# Sheet-watch.net
KiCad netlist of a schematic drawn in Altium Designer
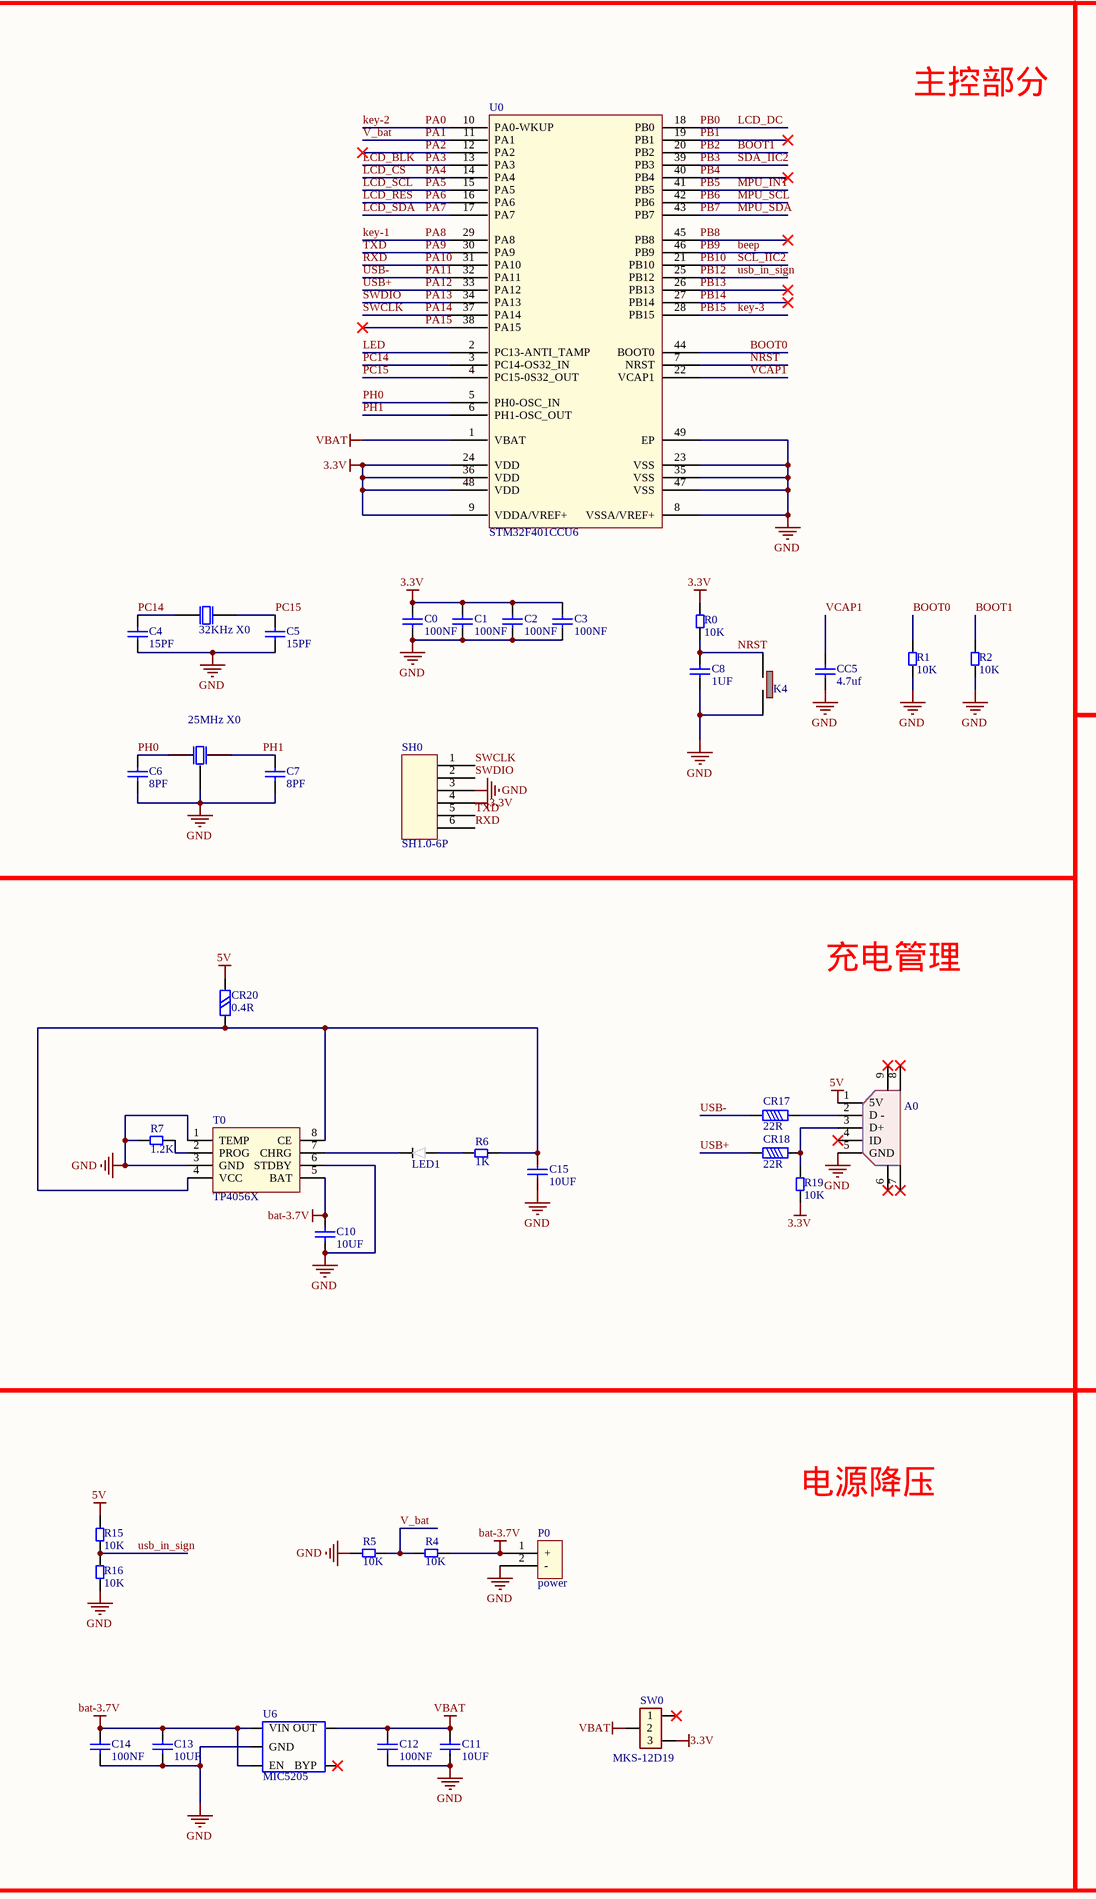
[diagram p0: Sheet-watch.SchDoc, left]
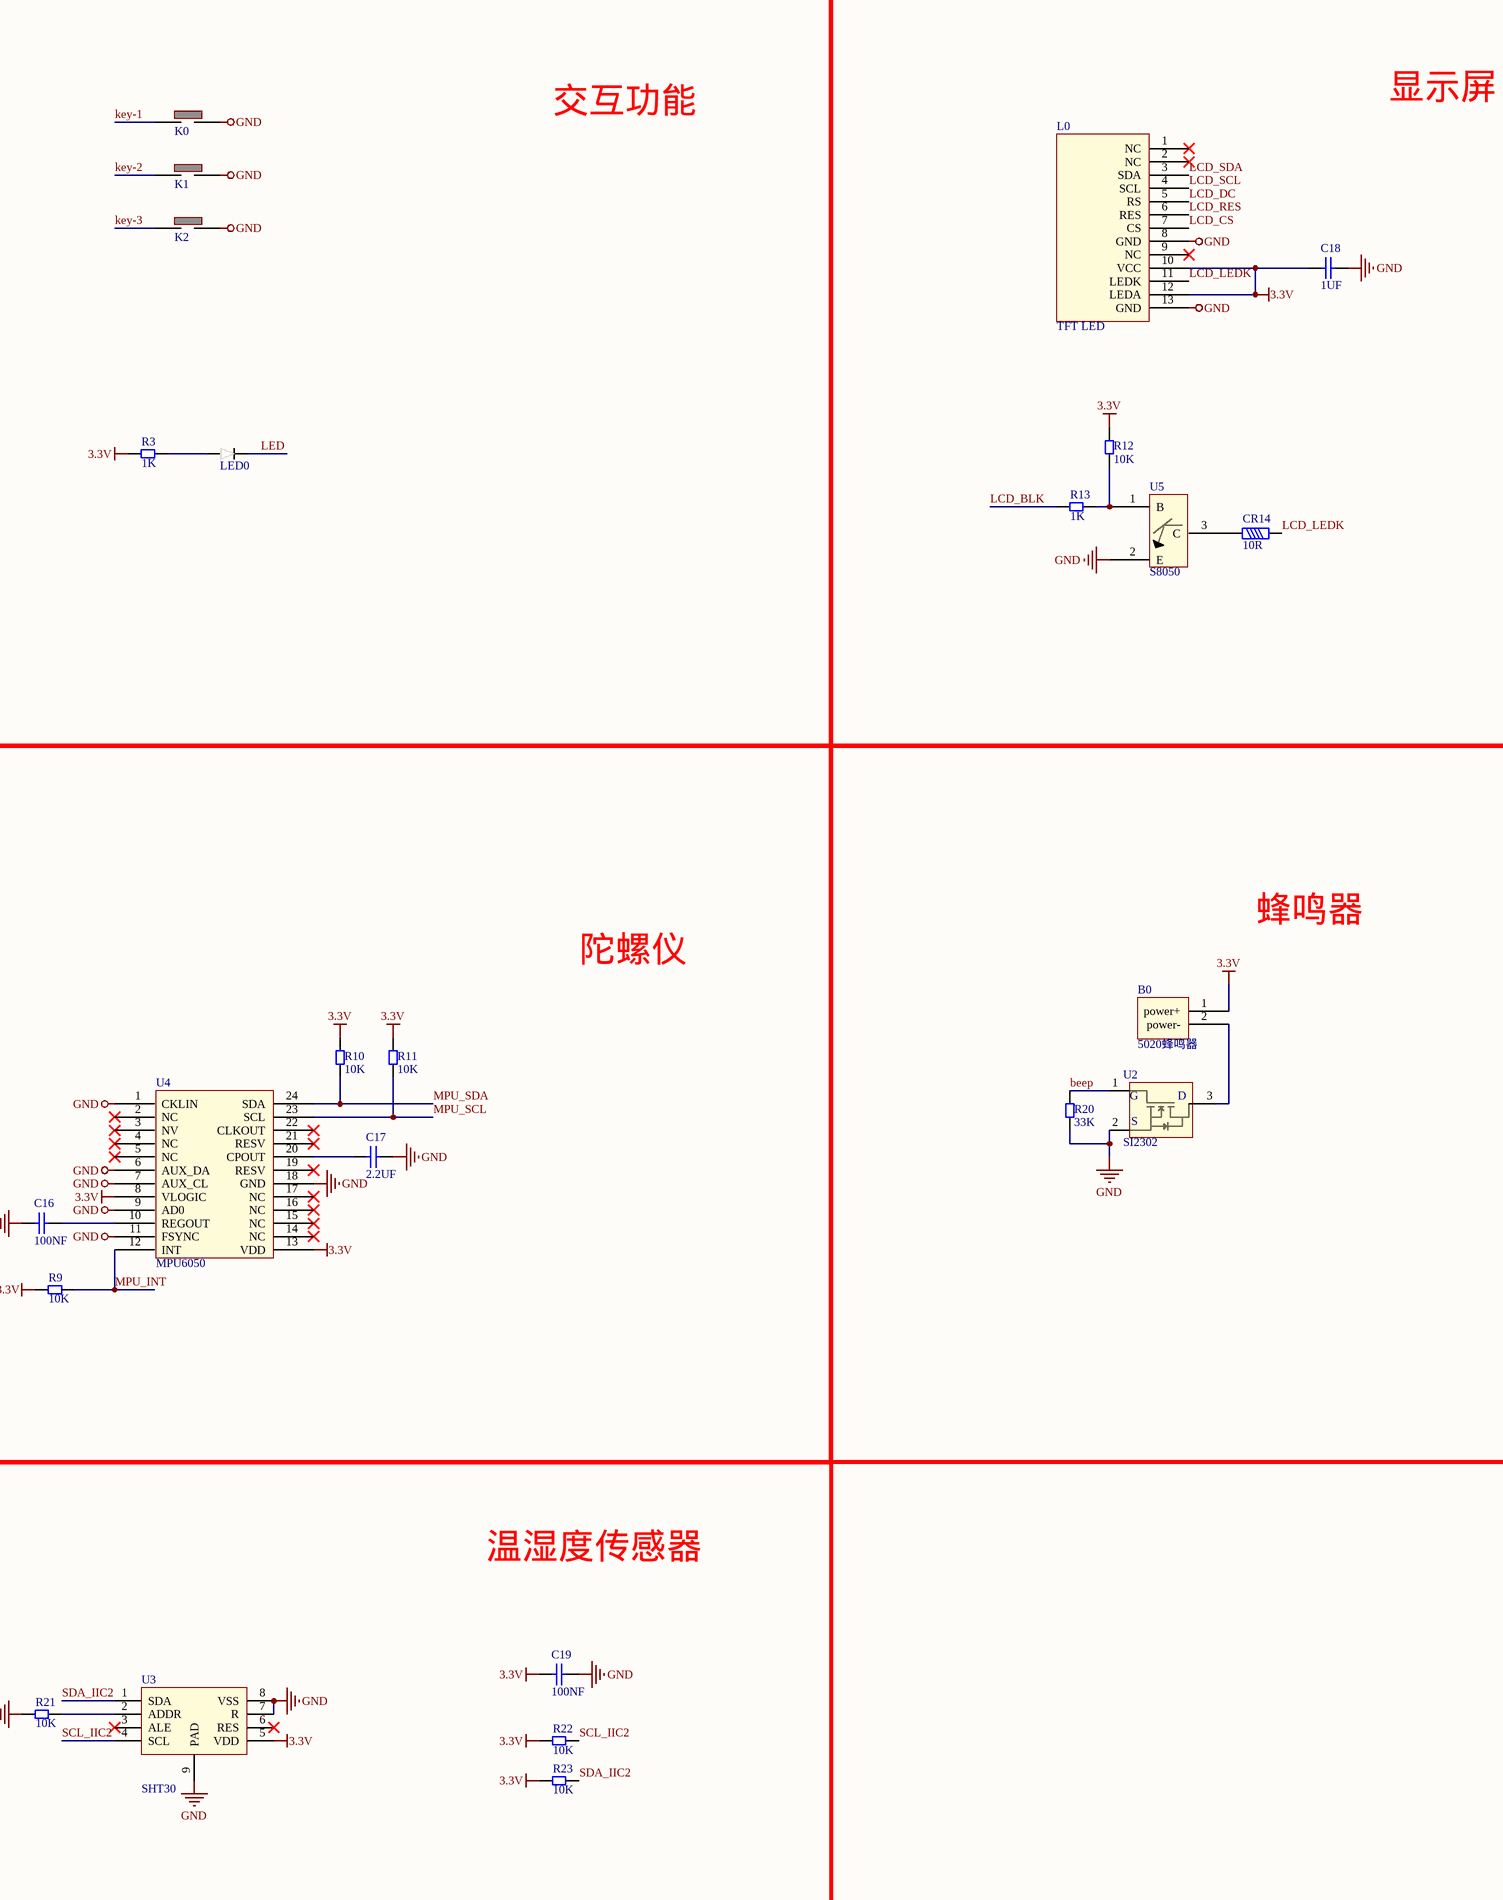
[diagram p1: Sheet-watch.SchDoc, right]

(export (version "E")
  (design (tool "Eeschema 10.0.6"))
  (components
    (comp (ref "25MHz X0")
      (value "XTAL 3225 8M")
      (footprint "T 3225")
      (libsource (lib "tianxiaohua_Schlib") (part "XTAL 3225 8M"))
    )
    (comp (ref "32KHz X0")
      (value "XTAL 3215 32.768kKHz")
      (footprint "T 3215")
      (libsource (lib "tianxiaohua_Schlib") (part "XTAL 3215 32.768kKHz"))
    )
    (comp (ref "A0")
      (value "Micro USB")
      (footprint "Micro usb AB")
      (libsource (lib "tianxiaohua_Schlib") (part "Micro USB"))
    )
    (comp (ref "B0")
      (value "5020蜂鸣器")
      (footprint "5020蜂鸣器")
      (description "蜂鸣器，贴片封装，长宽5.2mm")
      (libsource (lib "tianxiaohua_Schlib") (part "5020蜂鸣器"))
    )
    (comp (ref "C0")
      (value "100NF")
      (footprint "0402Capacitor")
      (libsource (lib "tianxiaohua_Schlib") (part "0402 CAP"))
    )
    (comp (ref "C1")
      (value "100NF")
      (footprint "0402Capacitor")
      (libsource (lib "tianxiaohua_Schlib") (part "0402 CAP"))
    )
    (comp (ref "C2")
      (value "100NF")
      (footprint "0402Capacitor")
      (libsource (lib "tianxiaohua_Schlib") (part "0402 CAP"))
    )
    (comp (ref "C3")
      (value "100NF")
      (footprint "0402Capacitor")
      (libsource (lib "tianxiaohua_Schlib") (part "0402 CAP"))
    )
    (comp (ref "C4")
      (value "15PF")
      (footprint "0402Capacitor")
      (libsource (lib "tianxiaohua_Schlib") (part "0402 CAP"))
    )
    (comp (ref "C5")
      (value "15PF")
      (footprint "0402Capacitor")
      (libsource (lib "tianxiaohua_Schlib") (part "0402 CAP"))
    )
    (comp (ref "C6")
      (value "8PF")
      (footprint "0402Capacitor")
      (libsource (lib "tianxiaohua_Schlib") (part "0402 CAP"))
    )
    (comp (ref "C7")
      (value "8PF")
      (footprint "0402Capacitor")
      (libsource (lib "tianxiaohua_Schlib") (part "0402 CAP"))
    )
    (comp (ref "C8")
      (value "1UF")
      (footprint "0402Capacitor")
      (libsource (lib "tianxiaohua_Schlib") (part "0402 CAP"))
    )
    (comp (ref "C10")
      (value "10UF")
      (footprint "0402Capacitor")
      (libsource (lib "tianxiaohua_Schlib") (part "0402 CAP"))
    )
    (comp (ref "C11")
      (value "10UF")
      (footprint "0402Capacitor")
      (libsource (lib "tianxiaohua_Schlib") (part "0402 CAP"))
    )
    (comp (ref "C12")
      (value "100NF")
      (footprint "0402Capacitor")
      (libsource (lib "tianxiaohua_Schlib") (part "0402 CAP"))
    )
    (comp (ref "C13")
      (value "10UF")
      (footprint "0402Capacitor")
      (libsource (lib "tianxiaohua_Schlib") (part "0402 CAP"))
    )
    (comp (ref "C14")
      (value "100NF")
      (footprint "0402Capacitor")
      (libsource (lib "tianxiaohua_Schlib") (part "0402 CAP"))
    )
    (comp (ref "C15")
      (value "10UF")
      (footprint "0402Capacitor")
      (libsource (lib "tianxiaohua_Schlib") (part "0402 CAP"))
    )
    (comp (ref "C16")
      (value "100NF")
      (footprint "0402Capacitor")
      (libsource (lib "tianxiaohua_Schlib") (part "0402 CAP"))
    )
    (comp (ref "C17")
      (value "2.2UF")
      (footprint "0402Capacitor")
      (libsource (lib "tianxiaohua_Schlib") (part "0402 CAP"))
    )
    (comp (ref "C18")
      (value "1UF")
      (footprint "0402Capacitor")
      (libsource (lib "tianxiaohua_Schlib") (part "0402 CAP"))
    )
    (comp (ref "C19")
      (value "100NF")
      (footprint "0402Capacitor")
      (libsource (lib "tianxiaohua_Schlib") (part "0402 CAP"))
    )
    (comp (ref "CC5")
      (value "4.7uf")
      (footprint "CC1608-0603")
      (description "Polarized Capacitor (Radial)")
      (fields (field (name "Comment") "Cap Chip 0603") (field (name "PUBLISHER") "Altium Limited"))
      (libsource (lib "tianxiaohua_Schlib") (part "Cap Chip 0603"))
    )
    (comp (ref "CR14")
      (value "10R")
      (footprint "CR1608-0603")
      (description "Resistor")
      (fields (field (name "Comment") "Resistor Chip 0603") (field (name "PUBLISHER") "Altium Limited"))
      (libsource (lib "tianxiaohua_Schlib") (part "Resistor Chip 0603"))
    )
    (comp (ref "CR17")
      (value "22R")
      (footprint "CR1608-0603")
      (description "Resistor")
      (fields (field (name "Comment") "Resistor Chip 0603") (field (name "PUBLISHER") "Altium Limited"))
      (libsource (lib "tianxiaohua_Schlib") (part "Resistor Chip 0603"))
    )
    (comp (ref "CR18")
      (value "22R")
      (footprint "CR1608-0603")
      (description "Resistor")
      (fields (field (name "Comment") "Resistor Chip 0603") (field (name "PUBLISHER") "Altium Limited"))
      (libsource (lib "tianxiaohua_Schlib") (part "Resistor Chip 0603"))
    )
    (comp (ref "CR20")
      (value "0.4R")
      (footprint "CR3216-1206")
      (description "Resistor")
      (fields (field (name "Comment") "Resistor Chip 1206") (field (name "PUBLISHER") "Altium Limited"))
      (libsource (lib "EButterflyIntegratedLibrary") (part "Resistor Chip 1206"))
    )
    (comp (ref "K0")
      (value "KEY 3*4")
      (footprint "2*4*3.5 KEY")
      (libsource (lib "tianxiaohua_Schlib") (part "KEY 3*4"))
    )
    (comp (ref "K1")
      (value "KEY 3*4")
      (footprint "2*4*3.5 KEY")
      (libsource (lib "tianxiaohua_Schlib") (part "KEY 3*4"))
    )
    (comp (ref "K2")
      (value "KEY 3*4")
      (footprint "2*4*3.5 KEY")
      (libsource (lib "tianxiaohua_Schlib") (part "KEY 3*4"))
    )
    (comp (ref "K4") (value "KEY 3*4") (footprint "KEY 3*4") (libsource (lib "") (part "KEY 3*4_1")))
    (comp (ref "L0")
      (value "TFT LED")
      (footprint "LCD-1.14IPS-(2)")
      (description "显示屏 1.14寸")
      (libsource (lib "tianxiaohua_Schlib") (part "LCD-IPSscreen"))
    )
    (comp (ref "LED0")
      (value "0402 LED")
      (footprint "0402 LED")
      (libsource (lib "tianxiaohua_Schlib") (part "0402 LED"))
    )
    (comp (ref "LED1")
      (value "0402 LED")
      (footprint "0402 LED")
      (libsource (lib "tianxiaohua_Schlib") (part "0402 LED"))
    )
    (comp (ref "P0")
      (value "power")
      (footprint "POWER-3.7V")
      (libsource (lib "tianxiaohua_Schlib") (part "power"))
    )
    (comp (ref "R0") (value "10K") (footprint "0402resistor") (libsource (lib "") (part "0402 RES_1")))
    (comp (ref "R1") (value "10K") (footprint "0402resistor") (libsource (lib "") (part "0402 RES_1")))
    (comp (ref "R2") (value "10K") (footprint "0402resistor") (libsource (lib "") (part "0402 RES_1")))
    (comp (ref "R3")
      (value "1K")
      (footprint "0402resistor")
      (libsource (lib "tianxiaohua_Schlib") (part "0402 RES"))
    )
    (comp (ref "R4")
      (value "10K")
      (footprint "0402resistor")
      (libsource (lib "tianxiaohua_Schlib") (part "0402 RES"))
    )
    (comp (ref "R5")
      (value "10K")
      (footprint "0402resistor")
      (libsource (lib "tianxiaohua_Schlib") (part "0402 RES"))
    )
    (comp (ref "R6")
      (value "1K")
      (footprint "0402resistor")
      (libsource (lib "tianxiaohua_Schlib") (part "0402 RES"))
    )
    (comp (ref "R7")
      (value "1.2K")
      (footprint "0402resistor")
      (libsource (lib "tianxiaohua_Schlib") (part "0402 RES"))
    )
    (comp (ref "R9")
      (value "10K")
      (footprint "0402resistor")
      (libsource (lib "tianxiaohua_Schlib") (part "0402 RES"))
    )
    (comp (ref "R10") (value "10K") (footprint "0402resistor") (libsource (lib "") (part "0402 RES_1")))
    (comp (ref "R11") (value "10K") (footprint "0402resistor") (libsource (lib "") (part "0402 RES_1")))
    (comp (ref "R12") (value "10K") (footprint "0402resistor") (libsource (lib "") (part "0402 RES_1")))
    (comp (ref "R13")
      (value "1K")
      (footprint "0402resistor")
      (libsource (lib "tianxiaohua_Schlib") (part "0402 RES"))
    )
    (comp (ref "R15") (value "10K") (footprint "0402resistor") (libsource (lib "") (part "0402 RES_1")))
    (comp (ref "R16") (value "10K") (footprint "0402resistor") (libsource (lib "") (part "0402 RES_1")))
    (comp (ref "R19") (value "10K") (footprint "0402resistor") (libsource (lib "") (part "0402 RES_1")))
    (comp (ref "R20") (value "33K") (footprint "0402resistor") (libsource (lib "") (part "0402 RES_1")))
    (comp (ref "R21")
      (value "10K")
      (footprint "0402resistor")
      (libsource (lib "tianxiaohua_Schlib") (part "0402 RES"))
    )
    (comp (ref "R22")
      (value "10K")
      (footprint "0402resistor")
      (libsource (lib "tianxiaohua_Schlib") (part "0402 RES"))
    )
    (comp (ref "R23")
      (value "10K")
      (footprint "0402resistor")
      (libsource (lib "tianxiaohua_Schlib") (part "0402 RES"))
    )
    (comp (ref "SH0")
      (value "SH1.0-6P")
      (footprint "SH1.0-6P")
      (description "间距为1mm的端子")
      (libsource (lib "tianxiaohua_Schlib") (part "SH1.0-6P"))
    )
    (comp (ref "SW0")
      (value "MKS-12D19")
      (footprint "SW  MSK-02")
      (libsource (lib "tianxiaohua_Schlib") (part "sw-MSK-12D19"))
    )
    (comp (ref "T0")
      (value "TP4056X")
      (footprint "ESOP8")
      (libsource (lib "tianxiaohua_Schlib") (part "TP4056X"))
    )
    (comp (ref "U0")
      (value "STM32F401CCU6")
      (footprint "STM32-UFQFPN48_N")
      (description "stm32单片机 主频100MHz")
      (libsource (lib "tianxiaohua_Schlib") (part "stm32F411CEU6"))
    )
    (comp (ref "U2")
      (value "SI2302")
      (footprint "SOT-23 SI2302")
      (description "NMOS场效应MOS管 SOT-23")
      (libsource (lib "tianxiaohua_Schlib") (part "SI2302"))
    )
    (comp (ref "U3")
      (value "SHT30")
      (footprint "SHT3X-DIS")
      (description "温湿度传感器")
      (libsource (lib "tianxiaohua_Schlib") (part "SHT30"))
    )
    (comp (ref "U4")
      (value "MPU6050")
      (footprint "QFN24 - duplicate")
      (description "陀螺仪")
      (libsource (lib "tianxiaohua_Schlib") (part "MPU6050"))
    )
    (comp (ref "U5")
      (value "S8050")
      (footprint "SOT-23 SI2302")
      (description "三极管放大管 NPN型三极管 大电流300ma")
      (libsource (lib "tianxiaohua_Schlib") (part "S8050"))
    )
    (comp (ref "U6")
      (value "MIC5205")
      (footprint "SOT23-5")
      (description "3.3V降压稳压芯片")
      (libsource (lib "tianxiaohua_Schlib") (part "MIC5205"))
    )
  )
  (nets
    (net (code "1") (name "/BOOT0") (class "Default")
      (node (ref "R1") (pin "2") (pinfunction "2_2") (pintype "passive"))
      (node (ref "U0") (pin "44") (pinfunction "BOOT0_44") (pintype "passive"))
    )
    (net (code "2") (name "/BOOT1") (class "Default")
      (node (ref "R2") (pin "2") (pinfunction "2_2") (pintype "passive"))
      (node (ref "U0") (pin "20") (pinfunction "PB2_20") (pintype "passive"))
    )
    (net (code "3") (name "/LCD_BLK") (class "Default")
      (node (ref "R13") (pin "2") (pinfunction "2_2") (pintype "passive"))
      (node (ref "U0") (pin "13") (pinfunction "PA3_13") (pintype "passive"))
    )
    (net (code "4") (name "/LCD_CS") (class "Default")
      (node (ref "L0") (pin "7") (pinfunction "CS_7") (pintype "passive"))
      (node (ref "U0") (pin "14") (pinfunction "PA4_14") (pintype "passive"))
    )
    (net (code "5") (name "/LCD_DC") (class "Default")
      (node (ref "L0") (pin "5") (pinfunction "RS_5") (pintype "passive"))
      (node (ref "U0") (pin "18") (pinfunction "PB0_18") (pintype "passive"))
    )
    (net (code "6") (name "/LCD_LEDK") (class "Default")
      (node (ref "CR14") (pin "2") (pinfunction "2_2") (pintype "passive"))
      (node (ref "L0") (pin "11") (pinfunction "LEDK_11") (pintype "passive"))
    )
    (net (code "7") (name "/LCD_RES") (class "Default")
      (node (ref "L0") (pin "6") (pinfunction "RES_6") (pintype "passive"))
      (node (ref "U0") (pin "16") (pinfunction "PA6_16") (pintype "passive"))
    )
    (net (code "8") (name "/LCD_SCL") (class "Default")
      (node (ref "L0") (pin "4") (pinfunction "SCL_4") (pintype "passive"))
      (node (ref "U0") (pin "15") (pinfunction "PA5_15") (pintype "passive"))
    )
    (net (code "9") (name "/LCD_SDA") (class "Default")
      (node (ref "L0") (pin "3") (pinfunction "SDA_3") (pintype "passive"))
      (node (ref "U0") (pin "17") (pinfunction "PA7_17") (pintype "passive"))
    )
    (net (code "10") (name "/LED") (class "Default")
      (node (ref "LED0") (pin "2") (pinfunction "2_2") (pintype "passive"))
      (node (ref "U0") (pin "2") (pinfunction "PC13-ANTI_TAMP_2") (pintype "passive"))
    )
    (net (code "11") (name "/MPU_INT") (class "Default")
      (node (ref "R9") (pin "1") (pinfunction "1_1") (pintype "passive"))
      (node (ref "U0") (pin "41") (pinfunction "PB5_41") (pintype "passive"))
      (node (ref "U4") (pin "12") (pinfunction "INT_12") (pintype "passive"))
    )
    (net (code "12") (name "/MPU_SCL") (class "Default")
      (node (ref "R11") (pin "1") (pinfunction "1_1") (pintype "passive"))
      (node (ref "U0") (pin "42") (pinfunction "PB6_42") (pintype "passive"))
      (node (ref "U4") (pin "23") (pinfunction "SCL_23") (pintype "passive"))
    )
    (net (code "13") (name "/MPU_SDA") (class "Default")
      (node (ref "R10") (pin "1") (pinfunction "1_1") (pintype "passive"))
      (node (ref "U0") (pin "43") (pinfunction "PB7_43") (pintype "passive"))
      (node (ref "U4") (pin "24") (pinfunction "SDA_24") (pintype "passive"))
    )
    (net (code "14") (name "/NRST") (class "Default")
      (node (ref "C8") (pin "2") (pinfunction "2_2") (pintype "passive"))
      (node (ref "K4") (pin "1") (pinfunction "1_1") (pintype "passive"))
      (node (ref "R0") (pin "1") (pinfunction "1_1") (pintype "passive"))
      (node (ref "U0") (pin "7") (pinfunction "NRST_7") (pintype "passive"))
    )
    (net (code "15") (name "/PA0") (class "Default")
      (node (ref "K1") (pin "1") (pinfunction "1_1") (pintype "passive"))
      (node (ref "U0") (pin "10") (pinfunction "PA0-WKUP_10") (pintype "passive"))
    )
    (net (code "16") (name "/PA1") (class "Default")
      (node (ref "R4") (pin "2") (pinfunction "2_2") (pintype "passive"))
      (node (ref "R5") (pin "1") (pinfunction "1_1") (pintype "passive"))
      (node (ref "U0") (pin "11") (pinfunction "PA1_11") (pintype "passive"))
    )
    (net (code "17") (name "/PA2") (class "Default")
      (node (ref "U0") (pin "12") (pinfunction "PA2_12") (pintype "passive+no_connect"))
    )
    (net (code "18") (name "/PA8") (class "Default")
      (node (ref "K0") (pin "1") (pinfunction "1_1") (pintype "passive"))
      (node (ref "U0") (pin "29") (pinfunction "PA8_29") (pintype "passive"))
    )
    (net (code "19") (name "/PA9") (class "Default")
      (node (ref "SH0") (pin "5") (pintype "passive"))
      (node (ref "U0") (pin "30") (pinfunction "PA9_30") (pintype "passive"))
    )
    (net (code "20") (name "/PA10") (class "Default")
      (node (ref "SH0") (pin "6") (pinfunction "6_6") (pintype "passive"))
      (node (ref "U0") (pin "31") (pinfunction "PA10_31") (pintype "passive"))
    )
    (net (code "21") (name "/PA11") (class "Default")
      (node (ref "CR17") (pin "1") (pinfunction "1_1") (pintype "passive"))
      (node (ref "U0") (pin "32") (pinfunction "PA11_32") (pintype "passive"))
    )
    (net (code "22") (name "/PA12") (class "Default")
      (node (ref "CR18") (pin "1") (pinfunction "1_1") (pintype "passive"))
      (node (ref "U0") (pin "33") (pinfunction "PA12_33") (pintype "passive"))
    )
    (net (code "23") (name "/PA13") (class "Default")
      (node (ref "SH0") (pin "2") (pinfunction "2_2") (pintype "passive"))
      (node (ref "U0") (pin "34") (pinfunction "PA13_34") (pintype "passive"))
    )
    (net (code "24") (name "/PA14") (class "Default")
      (node (ref "SH0") (pin "1") (pintype "passive"))
      (node (ref "U0") (pin "37") (pinfunction "PA14_37") (pintype "passive"))
    )
    (net (code "25") (name "/PA15") (class "Default")
      (node (ref "U0") (pin "38") (pinfunction "PA15_38") (pintype "passive+no_connect"))
    )
    (net (code "26") (name "/PB1") (class "Default")
      (node (ref "U0") (pin "19") (pinfunction "PB1_19") (pintype "passive+no_connect"))
    )
    (net (code "27") (name "/PB3") (class "Default")
      (node (ref "R23") (pin "1") (pinfunction "1_1") (pintype "passive"))
      (node (ref "U0") (pin "39") (pinfunction "PB3_39") (pintype "passive"))
      (node (ref "U3") (pin "1") (pinfunction "SDA_1") (pintype "passive"))
    )
    (net (code "28") (name "/PB4") (class "Default")
      (node (ref "U0") (pin "40") (pinfunction "PB4_40") (pintype "passive+no_connect"))
    )
    (net (code "29") (name "/PB8") (class "Default")
      (node (ref "U0") (pin "45") (pinfunction "PB8_45") (pintype "passive+no_connect"))
    )
    (net (code "30") (name "/PB9") (class "Default")
      (node (ref "R20") (pin "2") (pinfunction "2_2") (pintype "passive"))
      (node (ref "U0") (pin "46") (pinfunction "PB9_46") (pintype "passive"))
      (node (ref "U2") (pin "1") (pinfunction "GATE_1") (pintype "passive"))
    )
    (net (code "31") (name "/PB10") (class "Default")
      (node (ref "R22") (pin "1") (pinfunction "1_1") (pintype "passive"))
      (node (ref "U0") (pin "21") (pinfunction "PB10_21") (pintype "passive"))
      (node (ref "U3") (pin "4") (pinfunction "SCL_4") (pintype "passive"))
    )
    (net (code "32") (name "/PB12") (class "Default")
      (node (ref "R15") (pin "1") (pinfunction "1_1") (pintype "passive"))
      (node (ref "R16") (pin "2") (pinfunction "2_2") (pintype "passive"))
      (node (ref "U0") (pin "25") (pinfunction "PB12_25") (pintype "passive"))
    )
    (net (code "33") (name "/PB13") (class "Default")
      (node (ref "U0") (pin "26") (pinfunction "PB13_26") (pintype "passive+no_connect"))
    )
    (net (code "34") (name "/PB14") (class "Default")
      (node (ref "U0") (pin "27") (pinfunction "PB14_27") (pintype "passive+no_connect"))
    )
    (net (code "35") (name "/PB15") (class "Default")
      (node (ref "K2") (pin "1") (pinfunction "1_1") (pintype "passive"))
      (node (ref "U0") (pin "28") (pinfunction "PB15_28") (pintype "passive"))
    )
    (net (code "36") (name "/PC14") (class "Default")
      (node (ref "32KHz X0") (pin "1") (pinfunction "OSC1_1") (pintype "passive"))
      (node (ref "C4") (pin "2") (pinfunction "2_2") (pintype "passive"))
      (node (ref "U0") (pin "3") (pinfunction "PC14-OS32_IN_3") (pintype "passive"))
    )
    (net (code "37") (name "/PC15") (class "Default")
      (node (ref "32KHz X0") (pin "2") (pinfunction "OSC2_2") (pintype "passive"))
      (node (ref "C5") (pin "2") (pinfunction "2_2") (pintype "passive"))
      (node (ref "U0") (pin "4") (pinfunction "PC15-0S32_OUT_4") (pintype "passive"))
    )
    (net (code "38") (name "/PH0") (class "Default")
      (node (ref "25MHz X0") (pin "1") (pinfunction "OSC1_1") (pintype "passive"))
      (node (ref "C6") (pin "2") (pinfunction "2_2") (pintype "passive"))
      (node (ref "U0") (pin "5") (pinfunction "PH0-OSC_IN_5") (pintype "passive"))
    )
    (net (code "39") (name "/PH1") (class "Default")
      (node (ref "25MHz X0") (pin "2") (pinfunction "OSC2_2") (pintype "passive"))
      (node (ref "C7") (pin "2") (pinfunction "2_2") (pintype "passive"))
      (node (ref "U0") (pin "6") (pinfunction "PH1-OSC_OUT_6") (pintype "passive"))
    )
    (net (code "40") (name "/VCAP1") (class "Default")
      (node (ref "CC5") (pin "2") (pinfunction "2_2") (pintype "passive"))
      (node (ref "U0") (pin "22") (pinfunction "VCAP1_22") (pintype "passive"))
    )
    (net (code "41") (name "3.3V") (class "Default")
      (node (ref "B0") (pin "1") (pinfunction "power+_1") (pintype "passive"))
      (node (ref "C0") (pin "2") (pinfunction "2_2") (pintype "passive"))
      (node (ref "C1") (pin "2") (pinfunction "2_2") (pintype "passive"))
      (node (ref "C18") (pin "2") (pinfunction "2_2") (pintype "passive"))
      (node (ref "C19") (pin "2") (pinfunction "2_2") (pintype "passive"))
      (node (ref "C2") (pin "2") (pinfunction "2_2") (pintype "passive"))
      (node (ref "C3") (pin "2") (pinfunction "2_2") (pintype "passive"))
      (node (ref "L0") (pin "10") (pinfunction "VCC_10") (pintype "passive"))
      (node (ref "L0") (pin "12") (pinfunction "LEDA_12") (pintype "passive"))
      (node (ref "R0") (pin "2") (pinfunction "2_2") (pintype "passive"))
      (node (ref "R10") (pin "2") (pinfunction "2_2") (pintype "passive"))
      (node (ref "R11") (pin "2") (pinfunction "2_2") (pintype "passive"))
      (node (ref "R12") (pin "2") (pinfunction "2_2") (pintype "passive"))
      (node (ref "R19") (pin "1") (pinfunction "1_1") (pintype "passive"))
      (node (ref "R22") (pin "2") (pinfunction "2_2") (pintype "passive"))
      (node (ref "R23") (pin "2") (pinfunction "2_2") (pintype "passive"))
      (node (ref "R3") (pin "2") (pinfunction "2_2") (pintype "passive"))
      (node (ref "R9") (pin "2") (pinfunction "2_2") (pintype "passive"))
      (node (ref "SH0") (pin "4") (pinfunction "4_4") (pintype "passive"))
      (node (ref "SW0") (pin "3") (pinfunction "3_3") (pintype "passive"))
      (node (ref "U0") (pin "24") (pinfunction "VDD_24") (pintype "passive"))
      (node (ref "U0") (pin "36") (pinfunction "VDD_36") (pintype "passive"))
      (node (ref "U0") (pin "48") (pinfunction "VDD_48") (pintype "passive"))
      (node (ref "U0") (pin "9") (pinfunction "VDDA/VREF+_9") (pintype "passive"))
      (node (ref "U3") (pin "5") (pinfunction "VDD_5") (pintype "passive"))
      (node (ref "U4") (pin "13") (pinfunction "VDD_13") (pintype "passive"))
      (node (ref "U4") (pin "8") (pinfunction "VLOGIC_8") (pintype "passive"))
    )
    (net (code "42") (name "5V") (class "Default")
      (node (ref "A0") (pin "1") (pinfunction "5V_1") (pintype "passive"))
      (node (ref "CR20") (pin "2") (pinfunction "2_2") (pintype "passive"))
      (node (ref "R15") (pin "2") (pinfunction "2_2") (pintype "passive"))
    )
    (net (code "43") (name "GND") (class "Default")
      (node (ref "25MHz X0") (pin "3") (pinfunction "GND_3") (pintype "passive"))
      (node (ref "A0") (pin "5") (pinfunction "GND_5") (pintype "passive"))
      (node (ref "C0") (pin "1") (pinfunction "1_1") (pintype "passive"))
      (node (ref "C1") (pin "1") (pinfunction "1_1") (pintype "passive"))
      (node (ref "C10") (pin "1") (pinfunction "1_1") (pintype "passive"))
      (node (ref "C11") (pin "1") (pinfunction "1_1") (pintype "passive"))
      (node (ref "C12") (pin "1") (pinfunction "1_1") (pintype "passive"))
      (node (ref "C13") (pin "1") (pinfunction "1_1") (pintype "passive"))
      (node (ref "C14") (pin "1") (pinfunction "1_1") (pintype "passive"))
      (node (ref "C15") (pin "1") (pinfunction "1_1") (pintype "passive"))
      (node (ref "C16") (pin "2") (pinfunction "2_2") (pintype "passive"))
      (node (ref "C17") (pin "1") (pinfunction "1_1") (pintype "passive"))
      (node (ref "C18") (pin "1") (pinfunction "1_1") (pintype "passive"))
      (node (ref "C19") (pin "1") (pinfunction "1_1") (pintype "passive"))
      (node (ref "C2") (pin "1") (pinfunction "1_1") (pintype "passive"))
      (node (ref "C3") (pin "1") (pinfunction "1_1") (pintype "passive"))
      (node (ref "C4") (pin "1") (pinfunction "1_1") (pintype "passive"))
      (node (ref "C5") (pin "1") (pinfunction "1_1") (pintype "passive"))
      (node (ref "C6") (pin "1") (pinfunction "1_1") (pintype "passive"))
      (node (ref "C7") (pin "1") (pinfunction "1_1") (pintype "passive"))
      (node (ref "C8") (pin "1") (pinfunction "1_1") (pintype "passive"))
      (node (ref "CC5") (pin "1") (pinfunction "1_1") (pintype "passive"))
      (node (ref "K0") (pin "2") (pinfunction "2_2") (pintype "passive"))
      (node (ref "K1") (pin "2") (pinfunction "2_2") (pintype "passive"))
      (node (ref "K2") (pin "2") (pinfunction "2_2") (pintype "passive"))
      (node (ref "K4") (pin "2") (pinfunction "2_2") (pintype "passive"))
      (node (ref "L0") (pin "13") (pinfunction "GND_13") (pintype "passive"))
      (node (ref "L0") (pin "8") (pinfunction "GND_8") (pintype "passive"))
      (node (ref "P0") (pin "2") (pinfunction "-_2") (pintype "passive"))
      (node (ref "R1") (pin "1") (pinfunction "1_1") (pintype "passive"))
      (node (ref "R16") (pin "1") (pinfunction "1_1") (pintype "passive"))
      (node (ref "R2") (pin "1") (pinfunction "1_1") (pintype "passive"))
      (node (ref "R20") (pin "1") (pinfunction "1_1") (pintype "passive"))
      (node (ref "R21") (pin "2") (pinfunction "2_2") (pintype "passive"))
      (node (ref "R5") (pin "2") (pinfunction "2_2") (pintype "passive"))
      (node (ref "R7") (pin "2") (pinfunction "2_2") (pintype "passive"))
      (node (ref "SH0") (pin "3") (pintype "passive"))
      (node (ref "T0") (pin "1") (pinfunction "TEMP_1") (pintype "passive"))
      (node (ref "T0") (pin "3") (pinfunction "GND_3") (pintype "passive"))
      (node (ref "T0") (pin "6") (pinfunction "STDBY_6") (pintype "passive"))
      (node (ref "U0") (pin "23") (pinfunction "VSS_23") (pintype "passive"))
      (node (ref "U0") (pin "35") (pinfunction "VSS_35") (pintype "passive"))
      (node (ref "U0") (pin "47") (pinfunction "VSS_47") (pintype "passive"))
      (node (ref "U0") (pin "49") (pinfunction "EP_49") (pintype "passive"))
      (node (ref "U0") (pin "8") (pinfunction "VSSA/VREF+_8") (pintype "passive"))
      (node (ref "U2") (pin "2") (pinfunction "SOURCE_2") (pintype "passive"))
      (node (ref "U3") (pin "7") (pinfunction "R_7") (pintype "passive"))
      (node (ref "U3") (pin "8") (pinfunction "VSS_8") (pintype "passive"))
      (node (ref "U3") (pin "9") (pinfunction "PAD_9") (pintype "passive"))
      (node (ref "U4") (pin "1") (pinfunction "CKLIN_1") (pintype "passive"))
      (node (ref "U4") (pin "11") (pinfunction "FSYNC_11") (pintype "passive"))
      (node (ref "U4") (pin "18") (pinfunction "GND_18") (pintype "passive"))
      (node (ref "U4") (pin "6") (pinfunction "AUX_DA_6") (pintype "passive"))
      (node (ref "U4") (pin "7") (pinfunction "AUX_CL_7") (pintype "passive"))
      (node (ref "U4") (pin "9") (pinfunction "AD0_9") (pintype "passive"))
      (node (ref "U5") (pin "2") (pinfunction "E_2") (pintype "passive"))
      (node (ref "U6") (pin "2") (pinfunction "GND_2") (pintype "passive"))
    )
    (net (code "44") (name "Net-(A0-D+)") (class "Default")
      (node (ref "A0") (pin "3") (pinfunction "D+_3") (pintype "passive"))
      (node (ref "CR18") (pin "2") (pinfunction "2_2") (pintype "passive"))
      (node (ref "R19") (pin "2") (pinfunction "2_2") (pintype "passive"))
    )
    (net (code "45") (name "Net-(A0-D_-)") (class "Default")
      (node (ref "A0") (pin "2") (pinfunction "D_-_2") (pintype "passive"))
      (node (ref "CR17") (pin "2") (pinfunction "2_2") (pintype "passive"))
    )
    (net (code "46") (name "Net-(B0-power-)") (class "Default")
      (node (ref "B0") (pin "2") (pinfunction "power-_2") (pintype "passive"))
      (node (ref "U2") (pin "3") (pinfunction "DRAIN_3") (pintype "passive"))
    )
    (net (code "47") (name "Net-(LED0-Pad1)") (class "Default")
      (node (ref "LED0") (pin "1") (pinfunction "1_1") (pintype "passive"))
      (node (ref "R3") (pin "1") (pinfunction "1_1") (pintype "passive"))
    )
    (net (code "48") (name "Net-(LED1-Pad1)") (class "Default")
      (node (ref "LED1") (pin "1") (pinfunction "1_1") (pintype "passive"))
      (node (ref "R6") (pin "2") (pinfunction "2_2") (pintype "passive"))
    )
    (net (code "49") (name "Net-(T0-CE)") (class "Default")
      (node (ref "C15") (pin "2") (pinfunction "2_2") (pintype "passive"))
      (node (ref "CR20") (pin "1") (pinfunction "1_1") (pintype "passive"))
      (node (ref "R6") (pin "1") (pinfunction "1_1") (pintype "passive"))
      (node (ref "T0") (pin "4") (pinfunction "VCC_4") (pintype "passive"))
      (node (ref "T0") (pin "8") (pinfunction "CE_8") (pintype "passive"))
    )
    (net (code "50") (name "Net-(T0-CHRG)") (class "Default")
      (node (ref "LED1") (pin "2") (pinfunction "2_2") (pintype "passive"))
      (node (ref "T0") (pin "7") (pinfunction "CHRG_7") (pintype "passive"))
    )
    (net (code "51") (name "Net-(T0-PROG)") (class "Default")
      (node (ref "R7") (pin "1") (pinfunction "1_1") (pintype "passive"))
      (node (ref "T0") (pin "2") (pinfunction "PROG_2") (pintype "passive"))
    )
    (net (code "52") (name "Net-(U3-ADDR)") (class "Default")
      (node (ref "R21") (pin "1") (pinfunction "1_1") (pintype "passive"))
      (node (ref "U3") (pin "2") (pinfunction "ADDR_2") (pintype "passive"))
    )
    (net (code "53") (name "Net-(U4-CPOUT)") (class "Default")
      (node (ref "C17") (pin "2") (pinfunction "2_2") (pintype "passive"))
      (node (ref "U4") (pin "20") (pinfunction "CPOUT_20") (pintype "passive"))
    )
    (net (code "54") (name "Net-(U4-REGOUT)") (class "Default")
      (node (ref "C16") (pin "1") (pinfunction "1_1") (pintype "passive"))
      (node (ref "U4") (pin "10") (pinfunction "REGOUT_10") (pintype "passive"))
    )
    (net (code "55") (name "Net-(U5-B)") (class "Default")
      (node (ref "R12") (pin "1") (pinfunction "1_1") (pintype "passive"))
      (node (ref "R13") (pin "1") (pinfunction "1_1") (pintype "passive"))
      (node (ref "U5") (pin "1") (pinfunction "B_1") (pintype "passive"))
    )
    (net (code "56") (name "Net-(U5-C)") (class "Default")
      (node (ref "CR14") (pin "1") (pinfunction "1_1") (pintype "passive"))
      (node (ref "U5") (pin "3") (pinfunction "C_3") (pintype "passive"))
    )
    (net (code "57") (name "VBAT") (class "Default")
      (node (ref "C11") (pin "2") (pinfunction "2_2") (pintype "passive"))
      (node (ref "C12") (pin "2") (pinfunction "2_2") (pintype "passive"))
      (node (ref "SW0") (pin "2") (pinfunction "2_2") (pintype "passive"))
      (node (ref "U0") (pin "1") (pinfunction "VBAT_1") (pintype "passive"))
      (node (ref "U6") (pin "5") (pinfunction "OUT_5") (pintype "passive"))
    )
    (net (code "58") (name "bat-3.7V") (class "Default")
      (node (ref "C10") (pin "2") (pinfunction "2_2") (pintype "passive"))
      (node (ref "C13") (pin "2") (pinfunction "2_2") (pintype "passive"))
      (node (ref "C14") (pin "2") (pinfunction "2_2") (pintype "passive"))
      (node (ref "P0") (pin "1") (pinfunction "+_1") (pintype "passive"))
      (node (ref "R4") (pin "1") (pinfunction "1_1") (pintype "passive"))
      (node (ref "T0") (pin "5") (pinfunction "BAT_5") (pintype "passive"))
      (node (ref "U6") (pin "1") (pinfunction "VIN_1") (pintype "passive"))
      (node (ref "U6") (pin "3") (pinfunction "EN_3") (pintype "passive"))
    )
    (net (code "59") (name "unconnected-(A0-ID-Pad4)") (class "Default")
      (node (ref "A0") (pin "4") (pinfunction "ID_4") (pintype "passive+no_connect"))
    )
    (net (code "60") (name "unconnected-(A0-Pad6)") (class "Default")
      (node (ref "A0") (pin "6") (pinfunction "6_6") (pintype "passive+no_connect"))
    )
    (net (code "61") (name "unconnected-(A0-Pad7)") (class "Default")
      (node (ref "A0") (pin "7") (pinfunction "7_7") (pintype "passive+no_connect"))
    )
    (net (code "62") (name "unconnected-(A0-Pad8)") (class "Default")
      (node (ref "A0") (pin "8") (pinfunction "8_8") (pintype "passive+no_connect"))
    )
    (net (code "63") (name "unconnected-(A0-Pad9)") (class "Default")
      (node (ref "A0") (pin "9") (pinfunction "9_9") (pintype "passive+no_connect"))
    )
    (net (code "64") (name "unconnected-(L0-NC-Pad1)") (class "Default")
      (node (ref "L0") (pin "1") (pinfunction "NC_1") (pintype "passive+no_connect"))
    )
    (net (code "65") (name "unconnected-(L0-NC-Pad2)") (class "Default")
      (node (ref "L0") (pin "2") (pinfunction "NC_2") (pintype "passive+no_connect"))
    )
    (net (code "66") (name "unconnected-(L0-NC-Pad9)") (class "Default")
      (node (ref "L0") (pin "9") (pinfunction "NC_9") (pintype "passive+no_connect"))
    )
    (net (code "67") (name "unconnected-(SW0-Pad1)") (class "Default")
      (node (ref "SW0") (pin "1") (pinfunction "1_1") (pintype "passive+no_connect"))
    )
    (net (code "68") (name "unconnected-(U3-ALE-Pad3)") (class "Default")
      (node (ref "U3") (pin "3") (pinfunction "ALE_3") (pintype "passive+no_connect"))
    )
    (net (code "69") (name "unconnected-(U3-RES-Pad6)") (class "Default")
      (node (ref "U3") (pin "6") (pinfunction "RES_6") (pintype "passive+no_connect"))
    )
    (net (code "70") (name "unconnected-(U4-CLKOUT-Pad22)") (class "Default")
      (node (ref "U4") (pin "22") (pinfunction "CLKOUT_22") (pintype "passive+no_connect"))
    )
    (net (code "71") (name "unconnected-(U4-NC-Pad2)") (class "Default")
      (node (ref "U4") (pin "2") (pinfunction "NC_2") (pintype "passive+no_connect"))
    )
    (net (code "72") (name "unconnected-(U4-NC-Pad4)") (class "Default")
      (node (ref "U4") (pin "4") (pinfunction "NC_4") (pintype "passive+no_connect"))
    )
    (net (code "73") (name "unconnected-(U4-NC-Pad5)") (class "Default")
      (node (ref "U4") (pin "5") (pinfunction "NC_5") (pintype "passive+no_connect"))
    )
    (net (code "74") (name "unconnected-(U4-NC-Pad14)") (class "Default")
      (node (ref "U4") (pin "14") (pinfunction "NC_14") (pintype "passive+no_connect"))
    )
    (net (code "75") (name "unconnected-(U4-NC-Pad15)") (class "Default")
      (node (ref "U4") (pin "15") (pinfunction "NC_15") (pintype "passive+no_connect"))
    )
    (net (code "76") (name "unconnected-(U4-NC-Pad16)") (class "Default")
      (node (ref "U4") (pin "16") (pinfunction "NC_16") (pintype "passive+no_connect"))
    )
    (net (code "77") (name "unconnected-(U4-NC-Pad17)") (class "Default")
      (node (ref "U4") (pin "17") (pinfunction "NC_17") (pintype "passive+no_connect"))
    )
    (net (code "78") (name "unconnected-(U4-NV-Pad3)") (class "Default")
      (node (ref "U4") (pin "3") (pinfunction "NV_3") (pintype "passive+no_connect"))
    )
    (net (code "79") (name "unconnected-(U4-RESV-Pad19)") (class "Default")
      (node (ref "U4") (pin "19") (pinfunction "RESV_19") (pintype "passive+no_connect"))
    )
    (net (code "80") (name "unconnected-(U4-RESV-Pad21)") (class "Default")
      (node (ref "U4") (pin "21") (pinfunction "RESV_21") (pintype "passive+no_connect"))
    )
    (net (code "81") (name "unconnected-(U6-BYP-Pad4)") (class "Default")
      (node (ref "U6") (pin "4") (pinfunction "BYP_4") (pintype "passive+no_connect"))
    )
  )
)
